# Sch.net
KiCad netlist of a schematic drawn in Altium Designer
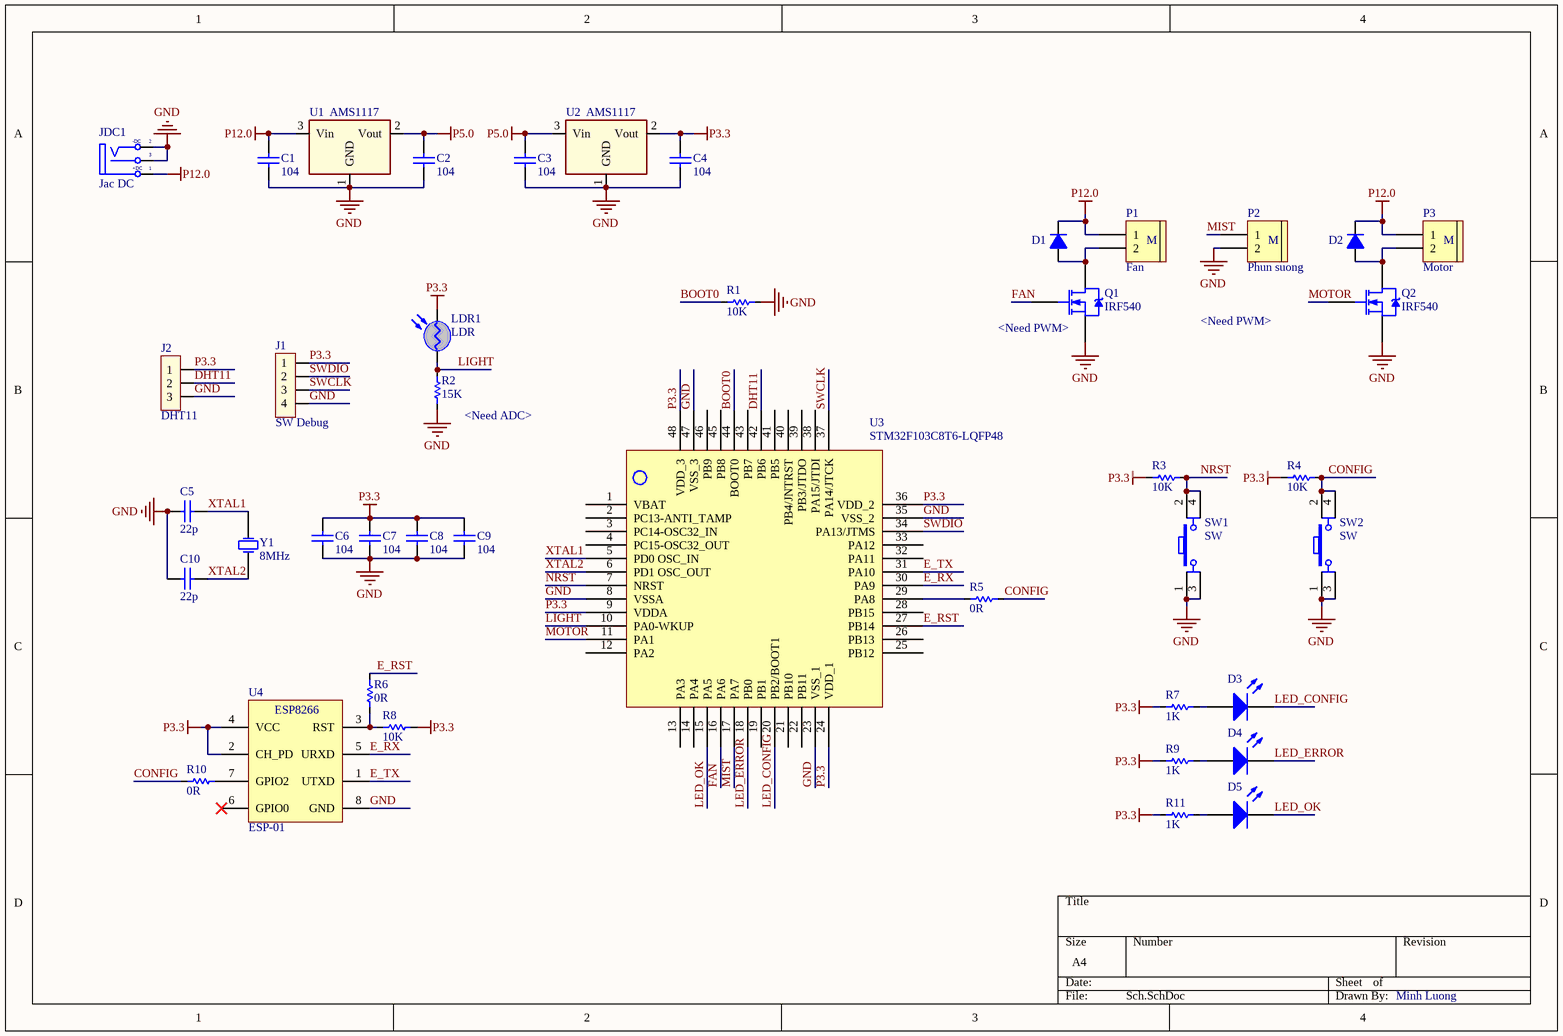
[diagram p0: Sch.SchDoc]

(export (version "E")
  (design (tool "Eeschema 10.0.6"))
  (components
    (comp (ref "C1")
      (value "104")
      (footprint "CAP_SMD_0805")
      (description "Non-polarized Capacitor")
      (fields (field (name "Comment") "Cap Non-pol") (field (name "PUBLISHER") "Altium Limited"))
      (libsource (lib "jmctvs") (part "Cap Non-pol"))
    )
    (comp (ref "C2")
      (value "104")
      (footprint "CAP_SMD_0805")
      (description "Non-polarized Capacitor")
      (fields (field (name "Comment") "Cap Non-pol") (field (name "PUBLISHER") "Altium Limited"))
      (libsource (lib "jmctvs") (part "Cap Non-pol"))
    )
    (comp (ref "C3")
      (value "104")
      (footprint "CAP_SMD_0805")
      (description "Non-polarized Capacitor")
      (fields (field (name "Comment") "Cap Non-pol") (field (name "PUBLISHER") "Altium Limited"))
      (libsource (lib "jmctvs") (part "Cap Non-pol"))
    )
    (comp (ref "C4")
      (value "104")
      (footprint "CAP_SMD_0805")
      (description "Non-polarized Capacitor")
      (fields (field (name "Comment") "Cap Non-pol") (field (name "PUBLISHER") "Altium Limited"))
      (libsource (lib "jmctvs") (part "Cap Non-pol"))
    )
    (comp (ref "C5")
      (value "22p")
      (footprint "CAP_SMD_0805")
      (description "Non-polarized Capacitor")
      (fields (field (name "Comment") "Cap Non-pol") (field (name "PUBLISHER") "Altium Limited"))
      (libsource (lib "jmctvs") (part "Cap Non-pol"))
    )
    (comp (ref "C6")
      (value "104")
      (footprint "CAP_SMD_0805")
      (description "Non-polarized Capacitor")
      (fields (field (name "Comment") "Cap Non-pol") (field (name "PUBLISHER") "Altium Limited"))
      (libsource (lib "jmctvs") (part "Cap Non-pol"))
    )
    (comp (ref "C7")
      (value "104")
      (footprint "CAP_SMD_0805")
      (description "Non-polarized Capacitor")
      (fields (field (name "Comment") "Cap Non-pol") (field (name "PUBLISHER") "Altium Limited"))
      (libsource (lib "jmctvs") (part "Cap Non-pol"))
    )
    (comp (ref "C8")
      (value "104")
      (footprint "CAP_SMD_0805")
      (description "Non-polarized Capacitor")
      (fields (field (name "Comment") "Cap Non-pol") (field (name "PUBLISHER") "Altium Limited"))
      (libsource (lib "jmctvs") (part "Cap Non-pol"))
    )
    (comp (ref "C9")
      (value "104")
      (footprint "CAP_SMD_0805")
      (description "Non-polarized Capacitor")
      (fields (field (name "Comment") "Cap Non-pol") (field (name "PUBLISHER") "Altium Limited"))
      (libsource (lib "jmctvs") (part "Cap Non-pol"))
    )
    (comp (ref "C10")
      (value "22p")
      (footprint "CAP_SMD_0805")
      (description "Non-polarized Capacitor")
      (fields (field (name "Comment") "Cap Non-pol") (field (name "PUBLISHER") "Altium Limited"))
      (libsource (lib "jmctvs") (part "Cap Non-pol"))
    )
    (comp (ref "D1")
      (value "Diode")
      (footprint "DO-41")
      (fields (field (name "PUBLISHER") "Altium Limited"))
      (libsource (lib "jmctvs") (part "Diode"))
    )
    (comp (ref "D2")
      (value "Diode")
      (footprint "DO-41")
      (fields (field (name "PUBLISHER") "Altium Limited"))
      (libsource (lib "jmctvs") (part "Diode"))
    )
    (comp (ref "D3")
      (value "LED")
      (footprint "LED-0805 BLUE")
      (description "Typical LED")
      (fields (field (name "PUBLISHER") "Altium Limited"))
      (libsource (lib "jmctvs") (part "LED"))
    )
    (comp (ref "D4")
      (value "LED")
      (footprint "LED-0805 RED")
      (description "Typical LED")
      (fields (field (name "PUBLISHER") "Altium Limited"))
      (libsource (lib "jmctvs") (part "LED"))
    )
    (comp (ref "D5")
      (value "LED")
      (footprint "LED-0805 GREEN")
      (description "Typical LED")
      (fields (field (name "PUBLISHER") "Altium Limited"))
      (libsource (lib "jmctvs") (part "LED"))
    )
    (comp (ref "J1") (value "SW Debug") (footprint "CON.HDR1X4") (libsource (lib "jmctvs") (part "JP4")))
    (comp (ref "J2")
      (value "DHT11")
      (footprint "JP3")
      (description "Jumper 3")
      (libsource (lib "jmctvs") (part "JP3"))
    )
    (comp (ref "JDC1")
      (value "Jac DC")
      (footprint "DC-IN")
      (description "Jac DC input")
      (libsource (lib "jmctvs") (part "DCIN"))
    )
    (comp (ref "LDR1")
      (value "LDR")
      (footprint "CDS")
      (description "Quang Tro")
      (libsource (lib "jmctvs") (part "LDR"))
    )
    (comp (ref "P1")
      (value "Fan")
      (footprint "Medium - Header 2")
      (description "Header, 2-Pin, Medium")
      (fields (field (name "PUBLISHER") "Altium Limited"))
      (libsource (lib "jmctvs") (part "Header 2 - M"))
    )
    (comp (ref "P2")
      (value "Phun suong")
      (footprint "Medium - Header 2")
      (description "Header, 2-Pin, Medium")
      (fields (field (name "PUBLISHER") "Altium Limited"))
      (libsource (lib "jmctvs") (part "Header 2 - M"))
    )
    (comp (ref "P3")
      (value "Motor")
      (footprint "Medium - Header 2")
      (description "Header, 2-Pin, Medium")
      (fields (field (name "PUBLISHER") "Altium Limited"))
      (libsource (lib "jmctvs") (part "Header 2 - M"))
    )
    (comp (ref "Q1")
      (value "IRF540")
      (footprint "TO-220-3")
      (description "HEXFET N-Channel Power MOSFET")
      (fields (field (name "PUBLISHER") "Altium Limited"))
      (libsource (lib "jmctvs") (part "IRF540"))
    )
    (comp (ref "Q2")
      (value "IRF540")
      (footprint "TO-220-3")
      (description "HEXFET N-Channel Power MOSFET")
      (fields (field (name "PUBLISHER") "Altium Limited"))
      (libsource (lib "jmctvs") (part "IRF540"))
    )
    (comp (ref "R1")
      (value "10K")
      (footprint "RES_SMD_0805")
      (description "Resistor")
      (fields (field (name "Comment") "RESISTOR") (field (name "PUBLISHER") "Altium Limited"))
      (libsource (lib "jmctvs") (part "RESISTOR"))
    )
    (comp (ref "R2")
      (value "15K")
      (footprint "RES_SMD_0805")
      (description "Resistor")
      (fields (field (name "Comment") "RESISTOR") (field (name "PUBLISHER") "Altium Limited"))
      (libsource (lib "jmctvs") (part "RESISTOR"))
    )
    (comp (ref "R3")
      (value "10K")
      (footprint "RES_SMD_0805")
      (description "Resistor")
      (fields (field (name "Comment") "RESISTOR") (field (name "PUBLISHER") "Altium Limited"))
      (libsource (lib "jmctvs") (part "RESISTOR"))
    )
    (comp (ref "R4")
      (value "10K")
      (footprint "RES_SMD_0805")
      (description "Resistor")
      (fields (field (name "Comment") "RESISTOR") (field (name "PUBLISHER") "Altium Limited"))
      (libsource (lib "jmctvs") (part "RESISTOR"))
    )
    (comp (ref "R5")
      (value "0R")
      (footprint "RES_SMD_0805")
      (description "Resistor")
      (fields (field (name "Comment") "RESISTOR") (field (name "PUBLISHER") "Altium Limited"))
      (libsource (lib "jmctvs") (part "RESISTOR"))
    )
    (comp (ref "R6")
      (value "0R")
      (footprint "RES_SMD_0805")
      (description "Resistor")
      (fields (field (name "Comment") "RESISTOR") (field (name "PUBLISHER") "Altium Limited"))
      (libsource (lib "jmctvs") (part "RESISTOR"))
    )
    (comp (ref "R7")
      (value "1K")
      (footprint "RES_SMD_0805")
      (description "Resistor")
      (fields (field (name "Comment") "RESISTOR") (field (name "PUBLISHER") "Altium Limited"))
      (libsource (lib "jmctvs") (part "RESISTOR"))
    )
    (comp (ref "R8")
      (value "10K")
      (footprint "RES_SMD_0805")
      (description "Resistor")
      (fields (field (name "Comment") "RESISTOR") (field (name "PUBLISHER") "Altium Limited"))
      (libsource (lib "jmctvs") (part "RESISTOR"))
    )
    (comp (ref "R9")
      (value "1K")
      (footprint "RES_SMD_0805")
      (description "Resistor")
      (fields (field (name "Comment") "RESISTOR") (field (name "PUBLISHER") "Altium Limited"))
      (libsource (lib "jmctvs") (part "RESISTOR"))
    )
    (comp (ref "R10")
      (value "0R")
      (footprint "RES_SMD_0805")
      (description "Resistor")
      (fields (field (name "Comment") "RESISTOR") (field (name "PUBLISHER") "Altium Limited"))
      (libsource (lib "jmctvs") (part "RESISTOR"))
    )
    (comp (ref "R11")
      (value "1K")
      (footprint "RES_SMD_0805")
      (description "Resistor")
      (fields (field (name "Comment") "RESISTOR") (field (name "PUBLISHER") "Altium Limited"))
      (libsource (lib "jmctvs") (part "RESISTOR"))
    )
    (comp (ref "SW1")
      (value "SW")
      (footprint "SW4")
      (description "Switch button 4 pin")
      (libsource (lib "jmctvs") (part "SW4"))
    )
    (comp (ref "SW2")
      (value "SW")
      (footprint "SW4")
      (description "Switch button 4 pin")
      (libsource (lib "jmctvs") (part "SW4"))
    )
    (comp (ref "U1")
      (value "AMS1117")
      (footprint "SOT223")
      (description "Regulator SMD Chip")
      (fields (field (name "DESIGNED BY") "John MacTavish"))
      (libsource (lib "jmctvs") (part "AMS1117"))
    )
    (comp (ref "U2")
      (value "AMS1117")
      (footprint "SOT223")
      (description "Regulator SMD Chip")
      (fields (field (name "DESIGNED BY") "John MacTavish"))
      (libsource (lib "jmctvs") (part "AMS1117"))
    )
    (comp (ref "U3")
      (value "STM32F103C8T6-LQFP48")
      (footprint "jmctvs:TQFP48L")
      (fields (field (name "PUBLISHER") "Altium Limited"))
      (libsource (lib "jmctvs") (part "STM32F103C8T6-LQFP48"))
    )
    (comp (ref "U4")
      (value "ESP-01")
      (footprint "jmctvs:ESP8266")
      (description "ESP-12 Wi-Fi Module")
      (libsource (lib "jmctvs") (part "ESP8266-01"))
    )
    (comp (ref "Y1")
      (value "8MHz")
      (footprint "XTAL")
      (description "Crystal Oscillator")
      (fields (field (name "PUBLISHER") "Altium Limited"))
      (libsource (lib "jmctvs") (part "XTAL"))
    )
  )
  (nets
    (net (code "1") (name "/BOOT0") (class "Default")
      (node (ref "R1") (pin "1") (pinfunction "1_1") (pintype "passive"))
      (node (ref "U3") (pin "44") (pinfunction "BOOT0_44") (pintype "passive"))
    )
    (net (code "2") (name "/CONFIG") (class "Default")
      (node (ref "R10") (pin "1") (pinfunction "1_1") (pintype "passive"))
      (node (ref "R4") (pin "1") (pinfunction "1_1") (pintype "passive"))
      (node (ref "R5") (pin "1") (pinfunction "1_1") (pintype "passive"))
      (node (ref "SW2") (pin "2") (pintype "passive"))
      (node (ref "SW2") (pin "4") (pintype "passive"))
    )
    (net (code "3") (name "/DHT11") (class "Default")
      (node (ref "J2") (pin "2") (pinfunction "2_2") (pintype "passive"))
      (node (ref "U3") (pin "42") (pinfunction "PB6_42") (pintype "passive"))
    )
    (net (code "4") (name "/E_RST") (class "Default")
      (node (ref "R6") (pin "1") (pinfunction "1_1") (pintype "passive"))
      (node (ref "U3") (pin "27") (pinfunction "PB14_27") (pintype "passive"))
    )
    (net (code "5") (name "/E_RX") (class "Default")
      (node (ref "U3") (pin "30") (pinfunction "PA9_30") (pintype "passive"))
      (node (ref "U4") (pin "5") (pinfunction "URXD_5") (pintype "passive"))
    )
    (net (code "6") (name "/E_TX") (class "Default")
      (node (ref "U3") (pin "31") (pinfunction "PA10_31") (pintype "passive"))
      (node (ref "U4") (pin "1") (pinfunction "UTXD_1") (pintype "passive"))
    )
    (net (code "7") (name "/FAN") (class "Default")
      (node (ref "Q1") (pin "1") (pinfunction "G_1") (pintype "passive"))
      (node (ref "U3") (pin "16") (pinfunction "PA6_16") (pintype "passive"))
    )
    (net (code "8") (name "/LED_CONFIG") (class "Default")
      (node (ref "D3") (pin "2") (pinfunction "K_2") (pintype "passive"))
      (node (ref "U3") (pin "20") (pinfunction "PB2/BOOT1_20") (pintype "passive"))
    )
    (net (code "9") (name "/LED_ERROR") (class "Default")
      (node (ref "D4") (pin "2") (pinfunction "K_2") (pintype "passive"))
      (node (ref "U3") (pin "18") (pinfunction "PB0_18") (pintype "passive"))
    )
    (net (code "10") (name "/LED_OK") (class "Default")
      (node (ref "D5") (pin "2") (pinfunction "K_2") (pintype "passive"))
      (node (ref "U3") (pin "15") (pinfunction "PA5_15") (pintype "passive"))
    )
    (net (code "11") (name "/LIGHT") (class "Default")
      (node (ref "LDR1") (pin "1") (pinfunction "A_1") (pintype "passive"))
      (node (ref "R2") (pin "1") (pinfunction "1_1") (pintype "passive"))
      (node (ref "U3") (pin "10") (pinfunction "PA0-WKUP_10") (pintype "passive"))
    )
    (net (code "12") (name "/MIST") (class "Default")
      (node (ref "P2") (pin "1") (pinfunction "1_1") (pintype "passive"))
      (node (ref "U3") (pin "17") (pinfunction "PA7_17") (pintype "passive"))
    )
    (net (code "13") (name "/MOTOR") (class "Default")
      (node (ref "Q2") (pin "1") (pinfunction "G_1") (pintype "passive"))
      (node (ref "U3") (pin "11") (pinfunction "PA1_11") (pintype "passive"))
    )
    (net (code "14") (name "/NRST") (class "Default")
      (node (ref "R3") (pin "1") (pinfunction "1_1") (pintype "passive"))
      (node (ref "SW1") (pin "2") (pintype "passive"))
      (node (ref "SW1") (pin "4") (pintype "passive"))
      (node (ref "U3") (pin "7") (pinfunction "NRST_7") (pintype "passive"))
    )
    (net (code "15") (name "/SWCLK") (class "Default")
      (node (ref "J1") (pin "3") (pinfunction "3_3") (pintype "passive"))
      (node (ref "U3") (pin "37") (pinfunction "PA14/JTCK_37") (pintype "passive"))
    )
    (net (code "16") (name "/SWDIO") (class "Default")
      (node (ref "J1") (pin "2") (pinfunction "2_2") (pintype "passive"))
      (node (ref "U3") (pin "34") (pinfunction "PA13/JTMS_34") (pintype "passive"))
    )
    (net (code "17") (name "/XTAL1") (class "Default")
      (node (ref "C5") (pin "2") (pinfunction "2_2") (pintype "passive"))
      (node (ref "U3") (pin "5") (pinfunction "PD0_OSC_IN_5") (pintype "passive"))
      (node (ref "Y1") (pin "2") (pinfunction "OSC2_2") (pintype "passive"))
    )
    (net (code "18") (name "/XTAL2") (class "Default")
      (node (ref "C10") (pin "2") (pinfunction "2_2") (pintype "passive"))
      (node (ref "U3") (pin "6") (pinfunction "PD1_OSC_OUT_6") (pintype "passive"))
      (node (ref "Y1") (pin "1") (pinfunction "OSC1_1") (pintype "passive"))
    )
    (net (code "19") (name "GND") (class "Default")
      (node (ref "C1") (pin "1") (pinfunction "1_1") (pintype "passive"))
      (node (ref "C10") (pin "1") (pinfunction "1_1") (pintype "passive"))
      (node (ref "C2") (pin "1") (pinfunction "1_1") (pintype "passive"))
      (node (ref "C3") (pin "1") (pinfunction "1_1") (pintype "passive"))
      (node (ref "C4") (pin "1") (pinfunction "1_1") (pintype "passive"))
      (node (ref "C5") (pin "1") (pinfunction "1_1") (pintype "passive"))
      (node (ref "C6") (pin "1") (pinfunction "1_1") (pintype "passive"))
      (node (ref "C7") (pin "1") (pinfunction "1_1") (pintype "passive"))
      (node (ref "C8") (pin "1") (pinfunction "1_1") (pintype "passive"))
      (node (ref "C9") (pin "1") (pinfunction "1_1") (pintype "passive"))
      (node (ref "J1") (pin "4") (pinfunction "4_4") (pintype "passive"))
      (node (ref "J2") (pin "3") (pinfunction "3_3") (pintype "passive"))
      (node (ref "JDC1") (pin "2") (pinfunction "TN_2") (pintype "passive"))
      (node (ref "JDC1") (pin "3") (pinfunction "S_3") (pintype "power_in"))
      (node (ref "P2") (pin "2") (pinfunction "2_2") (pintype "passive"))
      (node (ref "Q1") (pin "3") (pinfunction "S_3") (pintype "passive"))
      (node (ref "Q2") (pin "3") (pinfunction "S_3") (pintype "passive"))
      (node (ref "R1") (pin "2") (pinfunction "2_2") (pintype "passive"))
      (node (ref "R2") (pin "2") (pinfunction "2_2") (pintype "passive"))
      (node (ref "SW1") (pin "1") (pintype "passive"))
      (node (ref "SW1") (pin "3") (pintype "passive"))
      (node (ref "SW2") (pin "1") (pintype "passive"))
      (node (ref "SW2") (pin "3") (pintype "passive"))
      (node (ref "U1") (pin "1") (pinfunction "GND_1") (pintype "passive"))
      (node (ref "U2") (pin "1") (pinfunction "GND_1") (pintype "passive"))
      (node (ref "U3") (pin "23") (pinfunction "VSS_1_23") (pintype "passive"))
      (node (ref "U3") (pin "35") (pinfunction "VSS_2_35") (pintype "passive"))
      (node (ref "U3") (pin "47") (pinfunction "VSS_3_47") (pintype "passive"))
      (node (ref "U3") (pin "8") (pinfunction "VSSA_8") (pintype "passive"))
      (node (ref "U4") (pin "8") (pinfunction "GND_8") (pintype "passive"))
    )
    (net (code "20") (name "Net-(D1-A)") (class "Default")
      (node (ref "D1") (pin "1") (pinfunction "A_1") (pintype "passive"))
      (node (ref "P1") (pin "2") (pinfunction "2_2") (pintype "passive"))
      (node (ref "Q1") (pin "2") (pinfunction "D_2") (pintype "passive"))
    )
    (net (code "21") (name "Net-(D2-A)") (class "Default")
      (node (ref "D2") (pin "1") (pinfunction "A_1") (pintype "passive"))
      (node (ref "P3") (pin "2") (pinfunction "2_2") (pintype "passive"))
      (node (ref "Q2") (pin "2") (pinfunction "D_2") (pintype "passive"))
    )
    (net (code "22") (name "Net-(D3-A)") (class "Default")
      (node (ref "D3") (pin "1") (pinfunction "A_1") (pintype "passive"))
      (node (ref "R7") (pin "1") (pinfunction "1_1") (pintype "passive"))
    )
    (net (code "23") (name "Net-(D4-A)") (class "Default")
      (node (ref "D4") (pin "1") (pinfunction "A_1") (pintype "passive"))
      (node (ref "R9") (pin "1") (pinfunction "1_1") (pintype "passive"))
    )
    (net (code "24") (name "Net-(D5-A)") (class "Default")
      (node (ref "D5") (pin "1") (pinfunction "A_1") (pintype "passive"))
      (node (ref "R11") (pin "1") (pinfunction "1_1") (pintype "passive"))
    )
    (net (code "25") (name "Net-(U3-PA8)") (class "Default")
      (node (ref "R5") (pin "2") (pinfunction "2_2") (pintype "passive"))
      (node (ref "U3") (pin "29") (pinfunction "PA8_29") (pintype "passive"))
    )
    (net (code "26") (name "Net-(U4-GPIO2)") (class "Default")
      (node (ref "R10") (pin "2") (pinfunction "2_2") (pintype "passive"))
      (node (ref "U4") (pin "7") (pinfunction "GPIO2_7") (pintype "passive"))
    )
    (net (code "27") (name "Net-(U4-RST)") (class "Default")
      (node (ref "R6") (pin "2") (pinfunction "2_2") (pintype "passive"))
      (node (ref "R8") (pin "2") (pinfunction "2_2") (pintype "passive"))
      (node (ref "U4") (pin "3") (pinfunction "RST_3") (pintype "passive"))
    )
    (net (code "28") (name "P3.3") (class "Default")
      (node (ref "C4") (pin "2") (pinfunction "2_2") (pintype "passive"))
      (node (ref "C6") (pin "2") (pinfunction "2_2") (pintype "passive"))
      (node (ref "C7") (pin "2") (pinfunction "2_2") (pintype "passive"))
      (node (ref "C8") (pin "2") (pinfunction "2_2") (pintype "passive"))
      (node (ref "C9") (pin "2") (pinfunction "2_2") (pintype "passive"))
      (node (ref "J1") (pin "1") (pinfunction "1_1") (pintype "passive"))
      (node (ref "J2") (pin "1") (pinfunction "1_1") (pintype "passive"))
      (node (ref "LDR1") (pin "2") (pinfunction "K_2") (pintype "passive"))
      (node (ref "R11") (pin "2") (pinfunction "2_2") (pintype "passive"))
      (node (ref "R3") (pin "2") (pinfunction "2_2") (pintype "passive"))
      (node (ref "R4") (pin "2") (pinfunction "2_2") (pintype "passive"))
      (node (ref "R7") (pin "2") (pinfunction "2_2") (pintype "passive"))
      (node (ref "R8") (pin "1") (pinfunction "1_1") (pintype "passive"))
      (node (ref "R9") (pin "2") (pinfunction "2_2") (pintype "passive"))
      (node (ref "U2") (pin "2") (pinfunction "Vout_2") (pintype "passive"))
      (node (ref "U3") (pin "24") (pinfunction "VDD_1_24") (pintype "passive"))
      (node (ref "U3") (pin "36") (pinfunction "VDD_2_36") (pintype "passive"))
      (node (ref "U3") (pin "48") (pinfunction "VDD_3_48") (pintype "passive"))
      (node (ref "U3") (pin "9") (pinfunction "VDDA_9") (pintype "passive"))
      (node (ref "U4") (pin "2") (pinfunction "CH_PD_2") (pintype "passive"))
      (node (ref "U4") (pin "4") (pinfunction "VCC_4") (pintype "passive"))
    )
    (net (code "29") (name "P5.0") (class "Default")
      (node (ref "C2") (pin "2") (pinfunction "2_2") (pintype "passive"))
      (node (ref "C3") (pin "2") (pinfunction "2_2") (pintype "passive"))
      (node (ref "U1") (pin "2") (pinfunction "Vout_2") (pintype "passive"))
      (node (ref "U2") (pin "3") (pinfunction "Vin_3") (pintype "passive"))
    )
    (net (code "30") (name "P12.0") (class "Default")
      (node (ref "C1") (pin "2") (pinfunction "2_2") (pintype "passive"))
      (node (ref "D1") (pin "2") (pinfunction "K_2") (pintype "passive"))
      (node (ref "D2") (pin "2") (pinfunction "K_2") (pintype "passive"))
      (node (ref "JDC1") (pin "1") (pinfunction "T_1") (pintype "passive"))
      (node (ref "P1") (pin "1") (pinfunction "1_1") (pintype "passive"))
      (node (ref "P3") (pin "1") (pinfunction "1_1") (pintype "passive"))
      (node (ref "U1") (pin "3") (pinfunction "Vin_3") (pintype "passive"))
    )
    (net (code "31") (name "unconnected-(U3-PA2-Pad12)") (class "Default")
      (node (ref "U3") (pin "12") (pinfunction "PA2_12") (pintype "passive"))
    )
    (net (code "32") (name "unconnected-(U3-PA3-Pad13)") (class "Default")
      (node (ref "U3") (pin "13") (pinfunction "PA3_13") (pintype "passive"))
    )
    (net (code "33") (name "unconnected-(U3-PA4-Pad14)") (class "Default")
      (node (ref "U3") (pin "14") (pinfunction "PA4_14") (pintype "passive"))
    )
    (net (code "34") (name "unconnected-(U3-PA11-Pad32)") (class "Default")
      (node (ref "U3") (pin "32") (pinfunction "PA11_32") (pintype "passive"))
    )
    (net (code "35") (name "unconnected-(U3-PA12-Pad33)") (class "Default")
      (node (ref "U3") (pin "33") (pinfunction "PA12_33") (pintype "passive"))
    )
    (net (code "36") (name "unconnected-(U3-PA15{slash}JTDI-Pad38)") (class "Default")
      (node (ref "U3") (pin "38") (pinfunction "PA15/JTDI_38") (pintype "passive"))
    )
    (net (code "37") (name "unconnected-(U3-PB1-Pad19)") (class "Default")
      (node (ref "U3") (pin "19") (pinfunction "PB1_19") (pintype "passive"))
    )
    (net (code "38") (name "unconnected-(U3-PB3{slash}JTDO-Pad39)") (class "Default")
      (node (ref "U3") (pin "39") (pinfunction "PB3/JTDO_39") (pintype "passive"))
    )
    (net (code "39") (name "unconnected-(U3-PB4{slash}JNTRST-Pad40)") (class "Default")
      (node (ref "U3") (pin "40") (pinfunction "PB4/JNTRST_40") (pintype "passive"))
    )
    (net (code "40") (name "unconnected-(U3-PB5-Pad41)") (class "Default")
      (node (ref "U3") (pin "41") (pinfunction "PB5_41") (pintype "passive"))
    )
    (net (code "41") (name "unconnected-(U3-PB7-Pad43)") (class "Default")
      (node (ref "U3") (pin "43") (pinfunction "PB7_43") (pintype "passive"))
    )
    (net (code "42") (name "unconnected-(U3-PB8-Pad45)") (class "Default")
      (node (ref "U3") (pin "45") (pinfunction "PB8_45") (pintype "passive"))
    )
    (net (code "43") (name "unconnected-(U3-PB9-Pad46)") (class "Default")
      (node (ref "U3") (pin "46") (pinfunction "PB9_46") (pintype "passive"))
    )
    (net (code "44") (name "unconnected-(U3-PB10-Pad21)") (class "Default")
      (node (ref "U3") (pin "21") (pinfunction "PB10_21") (pintype "passive"))
    )
    (net (code "45") (name "unconnected-(U3-PB11-Pad22)") (class "Default")
      (node (ref "U3") (pin "22") (pinfunction "PB11_22") (pintype "passive"))
    )
    (net (code "46") (name "unconnected-(U3-PB12-Pad25)") (class "Default")
      (node (ref "U3") (pin "25") (pinfunction "PB12_25") (pintype "passive"))
    )
    (net (code "47") (name "unconnected-(U3-PB13-Pad26)") (class "Default")
      (node (ref "U3") (pin "26") (pinfunction "PB13_26") (pintype "passive"))
    )
    (net (code "48") (name "unconnected-(U3-PB15-Pad28)") (class "Default")
      (node (ref "U3") (pin "28") (pinfunction "PB15_28") (pintype "passive"))
    )
    (net (code "49") (name "unconnected-(U3-PC13-ANTI_TAMP-Pad2)") (class "Default")
      (node (ref "U3") (pin "2") (pinfunction "PC13-ANTI_TAMP_2") (pintype "passive"))
    )
    (net (code "50") (name "unconnected-(U3-PC14-OSC32_IN-Pad3)") (class "Default")
      (node (ref "U3") (pin "3") (pinfunction "PC14-OSC32_IN_3") (pintype "passive"))
    )
    (net (code "51") (name "unconnected-(U3-PC15-OSC32_OUT-Pad4)") (class "Default")
      (node (ref "U3") (pin "4") (pinfunction "PC15-OSC32_OUT_4") (pintype "passive"))
    )
    (net (code "52") (name "unconnected-(U3-VBAT-Pad1)") (class "Default")
      (node (ref "U3") (pin "1") (pinfunction "VBAT_1") (pintype "passive"))
    )
    (net (code "53") (name "unconnected-(U4-GPIO0-Pad6)") (class "Default")
      (node (ref "U4") (pin "6") (pinfunction "GPIO0_6") (pintype "passive+no_connect"))
    )
  )
)
